# BootCon.net
KiCad netlist of a schematic drawn in Altium Designer
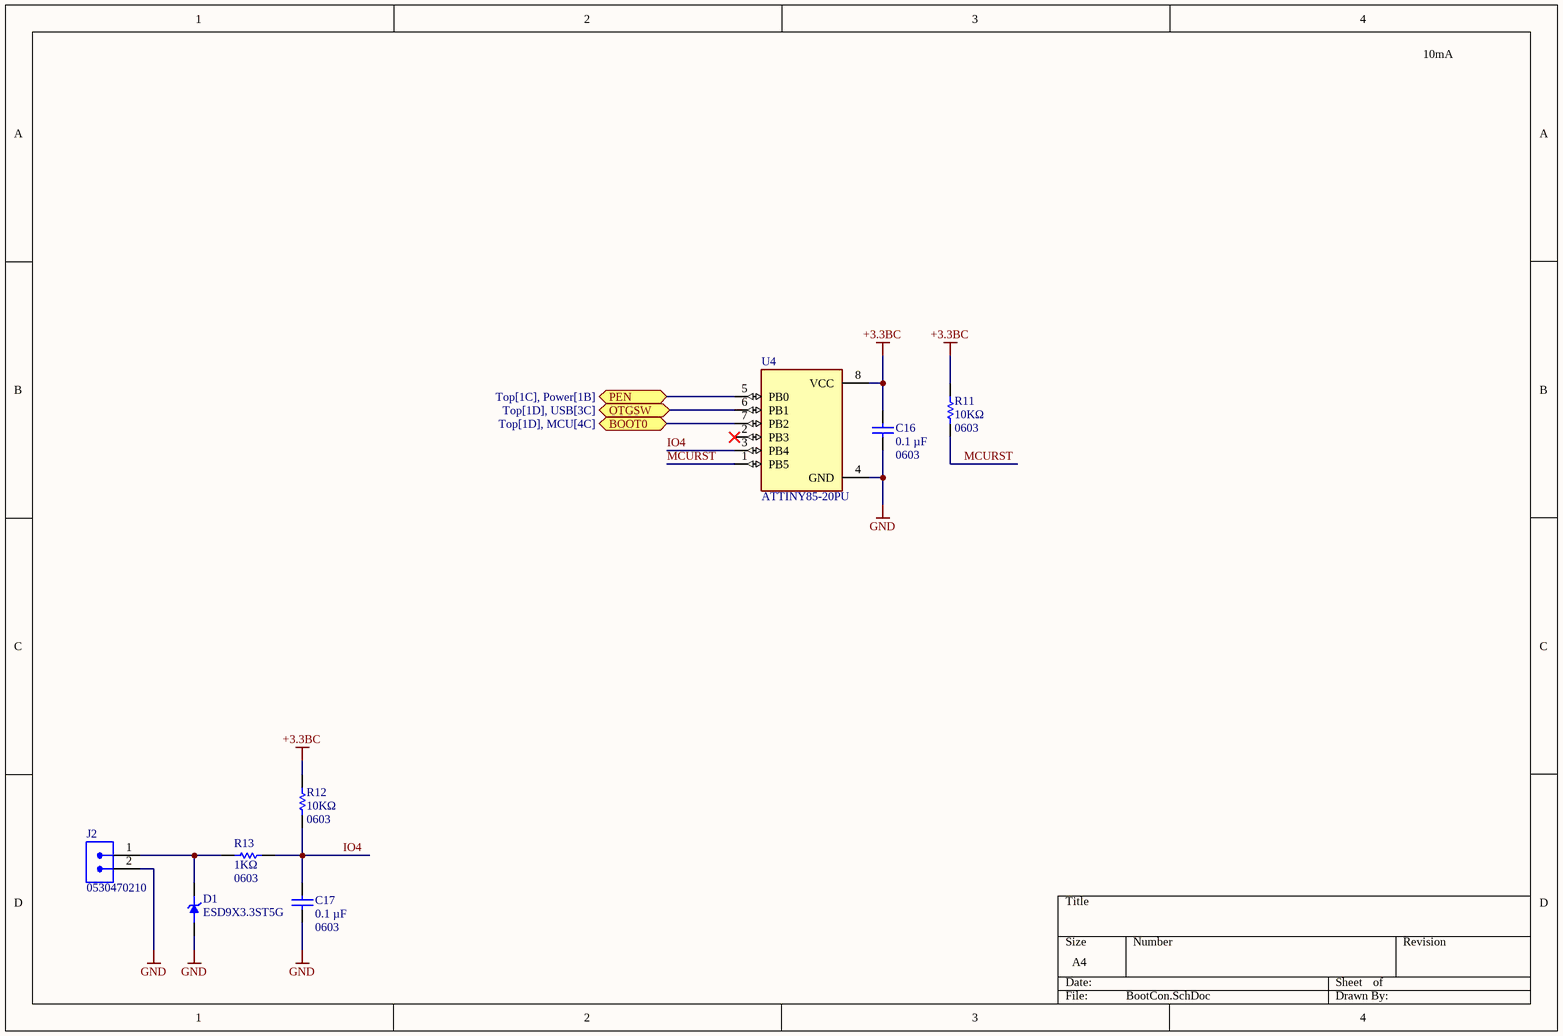
[diagram p0: BootCon.SchDoc]

(export (version "E")
  (design (tool "Eeschema 10.0.6"))
  (components
    (comp (ref "C16")
      (value "0.1 µF")
      (footprint "0603")
      (description "0.1 µF ±20% 100V Ceramic Capacitor X7R 0603 (1608 Metric)")
      (fields (field (name "CASE") "0603") (field (name "TOLERANCE") "±20%") (field (name "VOLTAGE") "100V"))
      (libsource (lib "Murata Electronics") (part "GRM188R72A104MA35J"))
    )
    (comp (ref "C17")
      (value "0.1 µF")
      (footprint "0603")
      (description "0.1 µF ±20% 100V Ceramic Capacitor X7R 0603 (1608 Metric)")
      (fields (field (name "CASE") "0603") (field (name "TOLERANCE") "±20%") (field (name "VOLTAGE") "100V"))
      (libsource (lib "Murata Electronics") (part "GRM188R72A104MA35J"))
    )
    (comp (ref "D1")
      (value "ESD9X3.3ST5G")
      (footprint "SOD923")
      (description "10.4V Clamp 9.8A (8/20µs) Ipp Tvs Diode Surface Mount SOD-923")
      (libsource (lib "Onsemi") (part "ESD9X3.3ST5G"))
    )
    (comp (ref "J2")
      (value "0530470210")
      (footprint "2POS")
      (description "Connector Header Through Hole 2 position 0.049\" (1.25mm)")
      (libsource (lib "Molex") (part "0530470210"))
    )
    (comp (ref "R11")
      (value "10KΩ")
      (footprint "0603")
      (description "10 kOhms ±1% 0.1W, 1/10W Chip Resistor 0603 (1608 Metric) Automotive AEC-Q200 Thick Film")
      (fields (field (name "CASE") "0603") (field (name "TOLERANCE") "1%") (field (name "POWER") "0.1W"))
      (libsource (lib "Stackpole Electronics Inc") (part "RMCF0603FG10K0"))
    )
    (comp (ref "R12")
      (value "10KΩ")
      (footprint "0603")
      (description "10 kOhms ±1% 0.1W, 1/10W Chip Resistor 0603 (1608 Metric) Automotive AEC-Q200 Thick Film")
      (fields (field (name "CASE") "0603") (field (name "TOLERANCE") "1%") (field (name "POWER") "0.1W"))
      (libsource (lib "Stackpole Electronics Inc") (part "RMCF0603FG10K0"))
    )
    (comp (ref "R13")
      (value "1KΩ")
      (footprint "0603")
      (description "1 kOhms ±1% 0.1W, 1/10W Chip Resistor 0603 (1608 Metric) Automotive AEC-Q200 Thick Film")
      (fields (field (name "CASE") "0603") (field (name "TOLERANCE") "1%") (field (name "POWER") "0.1W"))
      (libsource (lib "Stackpole Electronics Inc") (part "RMCF0603FG1K00"))
    )
    (comp (ref "U4")
      (value "ATTINY85-20PU")
      (footprint "DIP8")
      (libsource (lib "Microchip Technology") (part "ATTINY85-20PU"))
    )
  )
  (nets
    (net (code "1") (name "+3.3BC") (class "Default")
      (node (ref "C16") (pin "1") (pinfunction "1_1") (pintype "passive"))
      (node (ref "R11") (pin "2") (pinfunction "2_2") (pintype "passive"))
      (node (ref "R12") (pin "2") (pinfunction "2_2") (pintype "passive"))
      (node (ref "U4") (pin "8") (pinfunction "VCC_8") (pintype "power_in"))
    )
    (net (code "2") (name "/BOOT0") (class "Default")
      (node (ref "U4") (pin "7") (pinfunction "PB2_7") (pintype "bidirectional"))
    )
    (net (code "3") (name "/IO4") (class "Default")
      (node (ref "C17") (pin "1") (pinfunction "1_1") (pintype "passive"))
      (node (ref "R12") (pin "1") (pinfunction "1_1") (pintype "passive"))
      (node (ref "R13") (pin "1") (pinfunction "1_1") (pintype "passive"))
      (node (ref "U4") (pin "3") (pinfunction "PB4_3") (pintype "bidirectional"))
    )
    (net (code "4") (name "/MCURST") (class "Default")
      (node (ref "R11") (pin "1") (pinfunction "1_1") (pintype "passive"))
      (node (ref "U4") (pin "1") (pinfunction "PB5_1") (pintype "bidirectional"))
    )
    (net (code "5") (name "/OTGSW") (class "Default")
      (node (ref "U4") (pin "6") (pinfunction "PB1_6") (pintype "bidirectional"))
    )
    (net (code "6") (name "/PEN") (class "Default")
      (node (ref "U4") (pin "5") (pinfunction "PB0_5") (pintype "bidirectional"))
    )
    (net (code "7") (name "GND") (class "Default")
      (node (ref "C16") (pin "2") (pinfunction "2_2") (pintype "passive"))
      (node (ref "C17") (pin "2") (pinfunction "2_2") (pintype "passive"))
      (node (ref "D1") (pin "2") (pinfunction "A_2") (pintype "passive"))
      (node (ref "J2") (pin "2") (pinfunction "2_2") (pintype "passive"))
      (node (ref "U4") (pin "4") (pinfunction "GND_4") (pintype "power_in"))
    )
    (net (code "8") (name "Net-(D1-K)") (class "Default")
      (node (ref "D1") (pin "1") (pinfunction "K_1") (pintype "passive"))
      (node (ref "J2") (pin "1") (pinfunction "1_1") (pintype "passive"))
      (node (ref "R13") (pin "2") (pinfunction "2_2") (pintype "passive"))
    )
    (net (code "9") (name "unconnected-(U4-PB3-Pad2)") (class "Default")
      (node (ref "U4") (pin "2") (pinfunction "PB3_2") (pintype "bidirectional+no_connect"))
    )
  )
)
